# battery-shield-biginductor.net
KiCad netlist of a schematic drawn in EAGLE
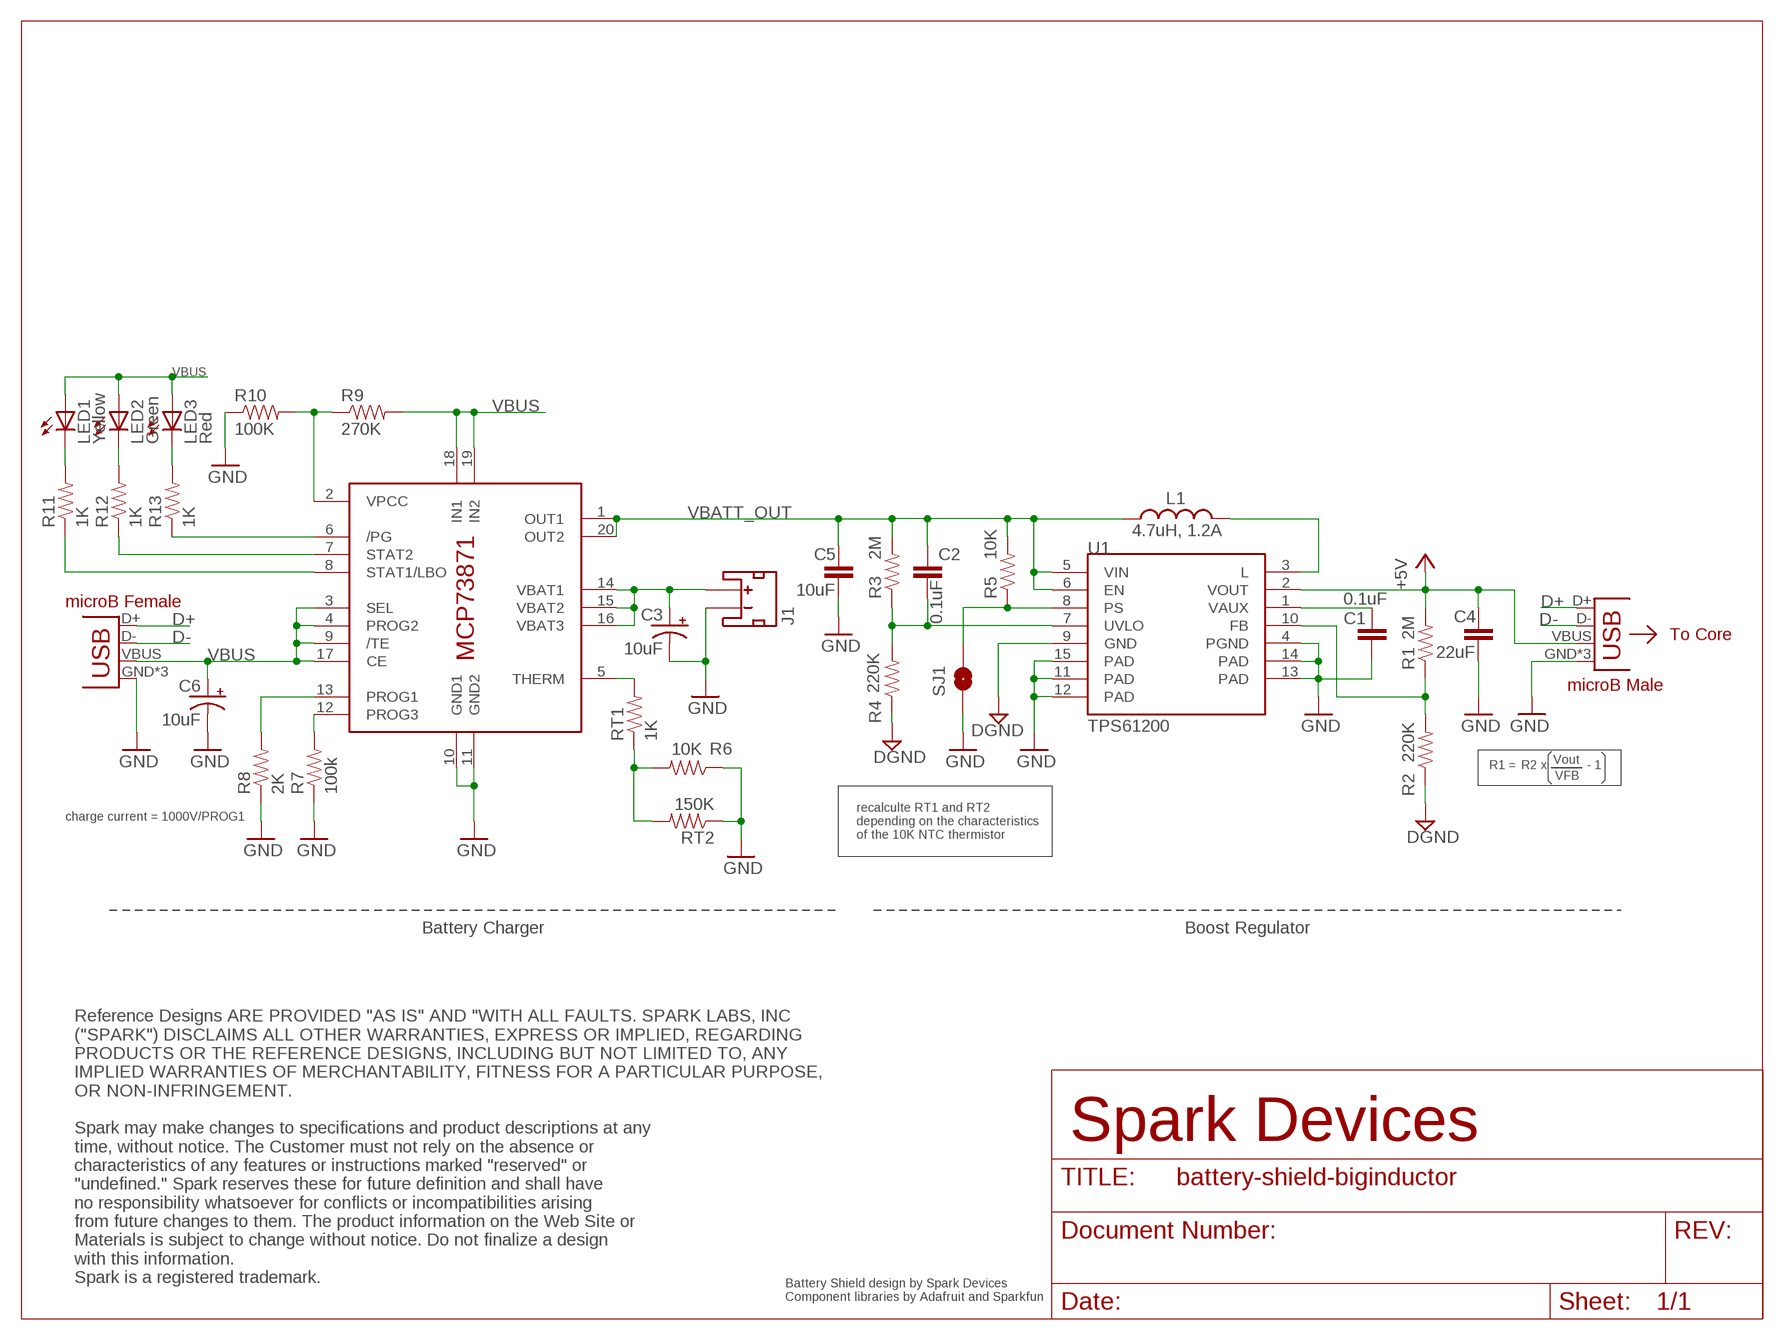
[diagram p0: schematic, sheet 1]

(export (version "E")
  (design (tool "Eeschema 10.0.6"))
  (components
    (comp (ref "C1")
      (value "0.1uF")
      (footprint "eagle-import:0402-CAP")
      (libsource (lib "eagle-import") (part "SparkFun-Passives_CAP0402-CAP"))
    )
    (comp (ref "C2")
      (value "0.1uF")
      (footprint "eagle-import:0402-CAP")
      (libsource (lib "eagle-import") (part "SparkFun-Passives_CAP0402-CAP"))
    )
    (comp (ref "C3")
      (value "10uF")
      (footprint "eagle-import:EIA3216")
      (libsource (lib "eagle-import") (part "10UF-16V-10%(TANT)"))
    )
    (comp (ref "C4")
      (value "22uF")
      (footprint "eagle-import:0805")
      (libsource (lib "eagle-import") (part "SparkFun-Passives_CAP0805"))
    )
    (comp (ref "C5")
      (value "10uF")
      (footprint "eagle-import:1206")
      (libsource (lib "eagle-import") (part "CAP1206"))
    )
    (comp (ref "C6")
      (value "10uF")
      (footprint "eagle-import:EIA3216")
      (fields (field (name "PROD_ID") "CAP-00811"))
      (libsource (lib "eagle-import") (part "10UF-16V-10%(TANT)"))
    )
    (comp (ref "IC1")
      (value "MCP73871")
      (footprint "eagle-import:QFN20")
      (libsource (lib "eagle-import") (part "MCP73871"))
    )
    (comp (ref "J1")
      (value "JST_2MM_MALE")
      (footprint "eagle-import:JST-2-SMD")
      (libsource (lib "eagle-import") (part "JST_2MM_MALE"))
    )
    (comp (ref "JP1")
      (value "USBUSB-MICROB-SLOT-HOLE")
      (footprint "eagle-import:USB-MICROB-SLOT-HOLE")
      (libsource (lib "eagle-import") (part "USBUSB-MICROB-SLOT-HOLE"))
    )
    (comp (ref "JP2")
      (value "USBFCI")
      (footprint "eagle-import:USB-MICROB-MALE-SANDWICH")
      (libsource (lib "eagle-import") (part "USBFCI"))
    )
    (comp (ref "L1")
      (value "4.7uH, 1.2A")
      (footprint "eagle-import:INDUCTOR-VLS-E")
      (libsource (lib "eagle-import") (part "INDUCTOR-SPARKFUNVLS3012ET-4R7M"))
    )
    (comp (ref "LED1")
      (value "Yellow")
      (footprint "eagle-import:LED-0603")
      (libsource (lib "eagle-import") (part "LED0603"))
    )
    (comp (ref "LED2")
      (value "Green")
      (footprint "eagle-import:LED-0603")
      (libsource (lib "eagle-import") (part "LED0603"))
    )
    (comp (ref "LED3")
      (value "Red")
      (footprint "eagle-import:LED-0603")
      (libsource (lib "eagle-import") (part "LED0603"))
    )
    (comp (ref "R1")
      (value "2M")
      (footprint "eagle-import:0402-RES")
      (libsource (lib "eagle-import") (part "RESISTOR0402-RES"))
    )
    (comp (ref "R2")
      (value "220K")
      (footprint "eagle-import:0402-RES")
      (libsource (lib "eagle-import") (part "RESISTOR0402-RES"))
    )
    (comp (ref "R3")
      (value "2M")
      (footprint "eagle-import:0402-RES")
      (libsource (lib "eagle-import") (part "RESISTOR0402-RES"))
    )
    (comp (ref "R4")
      (value "220K")
      (footprint "eagle-import:0402-RES")
      (libsource (lib "eagle-import") (part "RESISTOR0402-RES"))
    )
    (comp (ref "R5")
      (value "10K")
      (footprint "eagle-import:0402-RES")
      (libsource (lib "eagle-import") (part "RESISTOR0402-RES"))
    )
    (comp (ref "R6")
      (value "10K")
      (footprint "eagle-import:0402-RES")
      (libsource (lib "eagle-import") (part "RESISTOR0402-RES"))
    )
    (comp (ref "R7")
      (value "100k")
      (footprint "eagle-import:0402-RES")
      (libsource (lib "eagle-import") (part "RESISTOR0402-RES"))
    )
    (comp (ref "R8")
      (value "2K")
      (footprint "eagle-import:0402-RES")
      (libsource (lib "eagle-import") (part "RESISTOR0402-RES"))
    )
    (comp (ref "R9")
      (value "270K")
      (footprint "eagle-import:0402-RES")
      (libsource (lib "eagle-import") (part "RESISTOR0402-RES"))
    )
    (comp (ref "R10")
      (value "100K")
      (footprint "eagle-import:0402-RES")
      (libsource (lib "eagle-import") (part "RESISTOR0402-RES"))
    )
    (comp (ref "R11")
      (value "1K")
      (footprint "eagle-import:0402-RES")
      (libsource (lib "eagle-import") (part "RESISTOR0402-RES"))
    )
    (comp (ref "R12")
      (value "1K")
      (footprint "eagle-import:0402-RES")
      (libsource (lib "eagle-import") (part "RESISTOR0402-RES"))
    )
    (comp (ref "R13")
      (value "1K")
      (footprint "eagle-import:0402-RES")
      (libsource (lib "eagle-import") (part "RESISTOR0402-RES"))
    )
    (comp (ref "RT1")
      (value "1K")
      (footprint "eagle-import:0402-RES")
      (libsource (lib "eagle-import") (part "RESISTOR0402-RES"))
    )
    (comp (ref "RT2")
      (value "150K")
      (footprint "eagle-import:0402-RES")
      (libsource (lib "eagle-import") (part "RESISTOR0402-RES"))
    )
    (comp (ref "SJ1")
      (value "SOLDERJUMPERNO")
      (footprint "eagle-import:SJ_2S-NO")
      (libsource (lib "eagle-import") (part "SOLDERJUMPERNO"))
    )
    (comp (ref "U1")
      (value "TPS61200")
      (footprint "eagle-import:QFN-10_PAD")
      (libsource (lib "eagle-import") (part "TPS61200"))
    )
  )
  (nets
    (net (code "1") (name "+5V") (class "Default")
      (node (ref "C4") (pin "1") (pinfunction "1_1") (pintype "passive"))
      (node (ref "JP2") (pin "VBUS") (pinfunction "VBUS_VBUS") (pintype "bidirectional"))
      (node (ref "R1") (pin "2") (pinfunction "2_2") (pintype "passive"))
      (node (ref "U1") (pin "2") (pinfunction "VOUT_2") (pintype "passive"))
    )
    (net (code "2") (name "/D+") (class "Default")
      (node (ref "JP1") (pin "D+") (pinfunction "D+_D+") (pintype "bidirectional"))
      (node (ref "JP2") (pin "D+") (pinfunction "D+_D+") (pintype "bidirectional"))
    )
    (net (code "3") (name "/D-") (class "Default")
      (node (ref "JP1") (pin "D-") (pinfunction "D-_D-") (pintype "bidirectional"))
      (node (ref "JP2") (pin "D-") (pinfunction "D-_D-") (pintype "bidirectional"))
    )
    (net (code "4") (name "/VBATT_OUT") (class "Default")
      (node (ref "C2") (pin "1") (pinfunction "1_1") (pintype "passive"))
      (node (ref "C5") (pin "1") (pinfunction "1_1") (pintype "passive"))
      (node (ref "IC1") (pin "1") (pinfunction "OUT1_1") (pintype "output"))
      (node (ref "IC1") (pin "20") (pinfunction "OUT2_20") (pintype "output"))
      (node (ref "L1") (pin "P$1") (pinfunction "1_P$1") (pintype "passive"))
      (node (ref "R3") (pin "2") (pinfunction "2_2") (pintype "passive"))
      (node (ref "R5") (pin "2") (pinfunction "2_2") (pintype "passive"))
      (node (ref "U1") (pin "5") (pinfunction "VIN_5") (pintype "power_in"))
      (node (ref "U1") (pin "6") (pinfunction "EN_6") (pintype "input"))
    )
    (net (code "5") (name "/VBUS") (class "Default")
      (node (ref "C6") (pin "A") (pinfunction "+_A") (pintype "passive"))
      (node (ref "IC1") (pin "17") (pinfunction "CE_17") (pintype "input"))
      (node (ref "IC1") (pin "18") (pinfunction "IN1_18") (pintype "input"))
      (node (ref "IC1") (pin "19") (pinfunction "IN2_19") (pintype "input"))
      (node (ref "IC1") (pin "3") (pinfunction "SEL_3") (pintype "input"))
      (node (ref "IC1") (pin "4") (pinfunction "PROG2_4") (pintype "input"))
      (node (ref "IC1") (pin "9") (pinfunction "/TE_9") (pintype "input"))
      (node (ref "JP1") (pin "VBUS") (pinfunction "VBUS_VBUS") (pintype "bidirectional"))
      (node (ref "LED1") (pin "A") (pinfunction "A_A") (pintype "passive"))
      (node (ref "LED2") (pin "A") (pinfunction "A_A") (pintype "passive"))
      (node (ref "LED3") (pin "A") (pinfunction "A_A") (pintype "passive"))
      (node (ref "R9") (pin "2") (pinfunction "2_2") (pintype "passive"))
    )
    (net (code "6") (name "DGND") (class "Default")
      (node (ref "R2") (pin "1") (pinfunction "1_1") (pintype "passive"))
      (node (ref "R4") (pin "1") (pinfunction "1_1") (pintype "passive"))
      (node (ref "U1") (pin "9") (pinfunction "GND_9") (pintype "power_in"))
    )
    (net (code "7") (name "GND") (class "Default")
      (node (ref "C1") (pin "2") (pinfunction "2_2") (pintype "passive"))
      (node (ref "C3") (pin "C") (pinfunction "-_C") (pintype "passive"))
      (node (ref "C4") (pin "2") (pinfunction "2_2") (pintype "passive"))
      (node (ref "C5") (pin "2") (pinfunction "2_2") (pintype "passive"))
      (node (ref "C6") (pin "C") (pinfunction "-_C") (pintype "passive"))
      (node (ref "IC1") (pin "10") (pinfunction "GND1_10") (pintype "power_in"))
      (node (ref "IC1") (pin "11") (pinfunction "GND2_11") (pintype "power_in"))
      (node (ref "J1") (pin "1") (pinfunction "-_1") (pintype "bidirectional"))
      (node (ref "JP1") (pin "GND") (pinfunction "GND_GND") (pintype "bidirectional"))
      (node (ref "JP1") (pin "MT1") (pinfunction "GND_MT1") (pintype "bidirectional"))
      (node (ref "JP1") (pin "MT2") (pinfunction "GND_MT2") (pintype "bidirectional"))
      (node (ref "JP2") (pin "GND") (pinfunction "GND_GND") (pintype "bidirectional"))
      (node (ref "JP2") (pin "GNDPAD1") (pinfunction "GND_GNDPAD1") (pintype "bidirectional"))
      (node (ref "JP2") (pin "GNDPAD2") (pinfunction "GND_GNDPAD2") (pintype "bidirectional"))
      (node (ref "R10") (pin "1") (pinfunction "1_1") (pintype "passive"))
      (node (ref "R6") (pin "1") (pinfunction "1_1") (pintype "passive"))
      (node (ref "R7") (pin "1") (pinfunction "1_1") (pintype "passive"))
      (node (ref "R8") (pin "1") (pinfunction "1_1") (pintype "passive"))
      (node (ref "RT2") (pin "1") (pinfunction "1_1") (pintype "passive"))
      (node (ref "SJ1") (pin "1") (pinfunction "1_1") (pintype "passive"))
      (node (ref "U1") (pin "11") (pinfunction "PAD_11") (pintype "power_in"))
      (node (ref "U1") (pin "12") (pinfunction "PAD_12") (pintype "power_in"))
      (node (ref "U1") (pin "13") (pinfunction "PAD_13") (pintype "power_in"))
      (node (ref "U1") (pin "14") (pinfunction "PAD_14") (pintype "power_in"))
      (node (ref "U1") (pin "15") (pinfunction "PAD_15") (pintype "power_in"))
      (node (ref "U1") (pin "4") (pinfunction "PGND_4") (pintype "power_in"))
    )
    (net (code "8") (name "Net-(C3-+)") (class "Default")
      (node (ref "C3") (pin "A") (pinfunction "+_A") (pintype "passive"))
      (node (ref "IC1") (pin "14") (pinfunction "VBAT1_14") (pintype "output"))
      (node (ref "IC1") (pin "15") (pinfunction "VBAT2_15") (pintype "output"))
      (node (ref "IC1") (pin "16") (pinfunction "VBAT3_16") (pintype "output"))
      (node (ref "J1") (pin "2") (pinfunction "+_2") (pintype "bidirectional"))
    )
    (net (code "9") (name "Net-(IC1-PROG1)") (class "Default")
      (node (ref "IC1") (pin "13") (pinfunction "PROG1_13") (pintype "input"))
      (node (ref "R8") (pin "2") (pinfunction "2_2") (pintype "passive"))
    )
    (net (code "10") (name "Net-(IC1-PROG3)") (class "Default")
      (node (ref "IC1") (pin "12") (pinfunction "PROG3_12") (pintype "input"))
      (node (ref "R7") (pin "2") (pinfunction "2_2") (pintype "passive"))
    )
    (net (code "11") (name "Net-(IC1-STAT1{slash}LBO)") (class "Default")
      (node (ref "IC1") (pin "8") (pinfunction "STAT1/LBO_8") (pintype "output"))
      (node (ref "R11") (pin "1") (pinfunction "1_1") (pintype "passive"))
    )
    (net (code "12") (name "Net-(IC1-STAT2)") (class "Default")
      (node (ref "IC1") (pin "7") (pinfunction "STAT2_7") (pintype "output"))
      (node (ref "R12") (pin "1") (pinfunction "1_1") (pintype "passive"))
    )
    (net (code "13") (name "Net-(IC1-THERM)") (class "Default")
      (node (ref "IC1") (pin "5") (pinfunction "THERM_5") (pintype "input"))
      (node (ref "RT1") (pin "2") (pinfunction "2_2") (pintype "passive"))
    )
    (net (code "14") (name "Net-(IC1-VPCC)") (class "Default")
      (node (ref "IC1") (pin "2") (pinfunction "VPCC_2") (pintype "input"))
      (node (ref "R10") (pin "2") (pinfunction "2_2") (pintype "passive"))
      (node (ref "R9") (pin "1") (pinfunction "1_1") (pintype "passive"))
    )
    (net (code "15") (name "Net-(IC1-{slash}PG)") (class "Default")
      (node (ref "IC1") (pin "6") (pinfunction "/PG_6") (pintype "output"))
      (node (ref "R13") (pin "1") (pinfunction "1_1") (pintype "passive"))
    )
    (net (code "16") (name "Net-(L1-2)") (class "Default")
      (node (ref "L1") (pin "P$2") (pinfunction "2_P$2") (pintype "passive"))
      (node (ref "U1") (pin "3") (pinfunction "L_3") (pintype "passive"))
    )
    (net (code "17") (name "Net-(LED1-PadC)") (class "Default")
      (node (ref "LED1") (pin "C") (pinfunction "C_C") (pintype "passive"))
      (node (ref "R11") (pin "2") (pinfunction "2_2") (pintype "passive"))
    )
    (net (code "18") (name "Net-(LED2-PadC)") (class "Default")
      (node (ref "LED2") (pin "C") (pinfunction "C_C") (pintype "passive"))
      (node (ref "R12") (pin "2") (pinfunction "2_2") (pintype "passive"))
    )
    (net (code "19") (name "Net-(LED3-PadC)") (class "Default")
      (node (ref "LED3") (pin "C") (pinfunction "C_C") (pintype "passive"))
      (node (ref "R13") (pin "2") (pinfunction "2_2") (pintype "passive"))
    )
    (net (code "20") (name "Net-(R6-Pad2)") (class "Default")
      (node (ref "R6") (pin "2") (pinfunction "2_2") (pintype "passive"))
      (node (ref "RT1") (pin "1") (pinfunction "1_1") (pintype "passive"))
      (node (ref "RT2") (pin "2") (pinfunction "2_2") (pintype "passive"))
    )
    (net (code "21") (name "Net-(U1-FB)") (class "Default")
      (node (ref "R1") (pin "1") (pinfunction "1_1") (pintype "passive"))
      (node (ref "R2") (pin "2") (pinfunction "2_2") (pintype "passive"))
      (node (ref "U1") (pin "10") (pinfunction "FB_10") (pintype "passive"))
    )
    (net (code "22") (name "Net-(U1-PS)") (class "Default")
      (node (ref "R5") (pin "1") (pinfunction "1_1") (pintype "passive"))
      (node (ref "SJ1") (pin "2") (pinfunction "2_2") (pintype "passive"))
      (node (ref "U1") (pin "8") (pinfunction "PS_8") (pintype "input"))
    )
    (net (code "23") (name "Net-(U1-UVLO)") (class "Default")
      (node (ref "C2") (pin "2") (pinfunction "2_2") (pintype "passive"))
      (node (ref "R3") (pin "1") (pinfunction "1_1") (pintype "passive"))
      (node (ref "R4") (pin "2") (pinfunction "2_2") (pintype "passive"))
      (node (ref "U1") (pin "7") (pinfunction "UVLO_7") (pintype "passive"))
    )
    (net (code "24") (name "Net-(U1-VAUX)") (class "Default")
      (node (ref "C1") (pin "1") (pinfunction "1_1") (pintype "passive"))
      (node (ref "U1") (pin "1") (pinfunction "VAUX_1") (pintype "passive"))
    )
    (net (code "25") (name "unconnected-(J1-PAD1-PadNC1)") (class "Default")
      (node (ref "J1") (pin "NC1") (pinfunction "PAD1_NC1") (pintype "bidirectional"))
    )
    (net (code "26") (name "unconnected-(J1-PAD2-PadNC2)") (class "Default")
      (node (ref "J1") (pin "NC2") (pinfunction "PAD2_NC2") (pintype "bidirectional"))
    )
  )
)
